# UCirKitUserStudy5-3.net
KiCad netlist of a schematic drawn in EAGLE
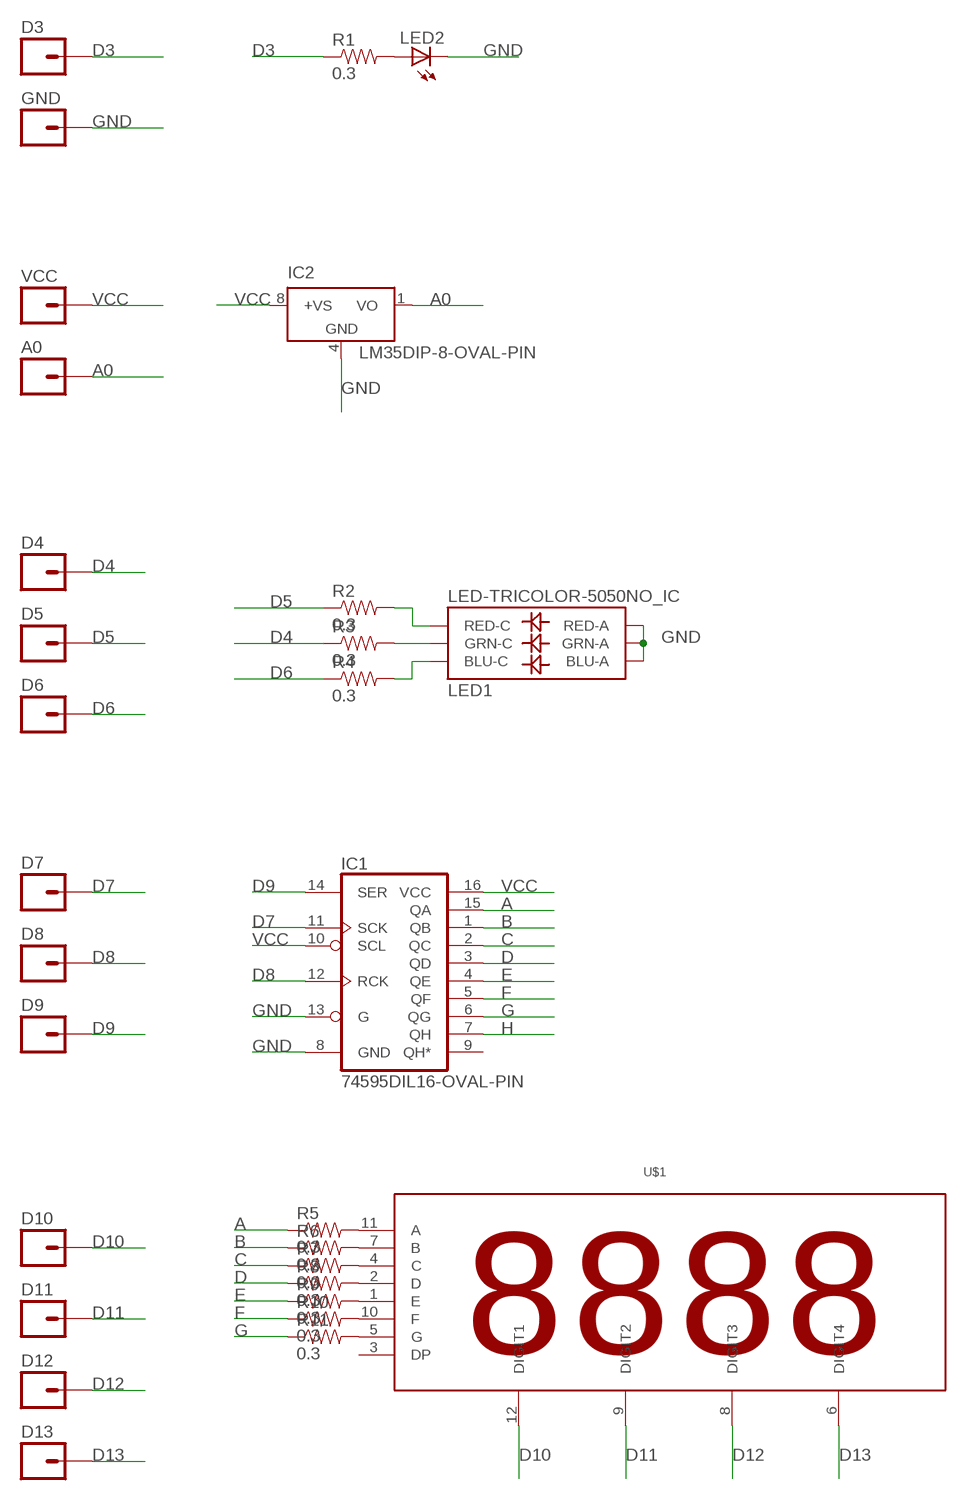
[diagram p0: schematic, sheet 1]

(export (version "E")
  (design (tool "Eeschema 10.0.6"))
  (components
    (comp (ref "A0")
      (value "M01OVAL_PIN")
      (footprint "eagle-import:1X01_OVAL_PIN")
      (libsource (lib "eagle-import") (part "M01OVAL_PIN"))
    )
    (comp (ref "D3")
      (value "M01OVAL_PIN")
      (footprint "eagle-import:1X01_OVAL_PIN")
      (libsource (lib "eagle-import") (part "M01OVAL_PIN"))
    )
    (comp (ref "D4")
      (value "M01OVAL_PIN")
      (footprint "eagle-import:1X01_OVAL_PIN")
      (libsource (lib "eagle-import") (part "M01OVAL_PIN"))
    )
    (comp (ref "D5")
      (value "M01OVAL_PIN")
      (footprint "eagle-import:1X01_OVAL_PIN")
      (libsource (lib "eagle-import") (part "M01OVAL_PIN"))
    )
    (comp (ref "D6")
      (value "M01OVAL_PIN")
      (footprint "eagle-import:1X01_OVAL_PIN")
      (libsource (lib "eagle-import") (part "M01OVAL_PIN"))
    )
    (comp (ref "D7")
      (value "M01OVAL_PIN")
      (footprint "eagle-import:1X01_OVAL_PIN")
      (libsource (lib "eagle-import") (part "M01OVAL_PIN"))
    )
    (comp (ref "D8")
      (value "M01OVAL_PIN")
      (footprint "eagle-import:1X01_OVAL_PIN")
      (libsource (lib "eagle-import") (part "M01OVAL_PIN"))
    )
    (comp (ref "D9")
      (value "M01OVAL_PIN")
      (footprint "eagle-import:1X01_OVAL_PIN")
      (libsource (lib "eagle-import") (part "M01OVAL_PIN"))
    )
    (comp (ref "D10")
      (value "M01OVAL_PIN")
      (footprint "eagle-import:1X01_OVAL_PIN")
      (libsource (lib "eagle-import") (part "M01OVAL_PIN"))
    )
    (comp (ref "D11")
      (value "M01OVAL_PIN")
      (footprint "eagle-import:1X01_OVAL_PIN")
      (libsource (lib "eagle-import") (part "M01OVAL_PIN"))
    )
    (comp (ref "D12")
      (value "M01OVAL_PIN")
      (footprint "eagle-import:1X01_OVAL_PIN")
      (libsource (lib "eagle-import") (part "M01OVAL_PIN"))
    )
    (comp (ref "D13")
      (value "M01OVAL_PIN")
      (footprint "eagle-import:1X01_OVAL_PIN")
      (libsource (lib "eagle-import") (part "M01OVAL_PIN"))
    )
    (comp (ref "GND")
      (value "M01OVAL_PIN")
      (footprint "eagle-import:1X01_OVAL_PIN")
      (libsource (lib "eagle-import") (part "M01OVAL_PIN"))
    )
    (comp (ref "IC1")
      (value "74595DIL16-OVAL-PIN")
      (footprint "eagle-import:DIL16-OVAL-PIN")
      (libsource (lib "eagle-import") (part "74595DIL16-OVAL-PIN"))
    )
    (comp (ref "IC2")
      (value "LM35DIP-8-OVAL-PIN")
      (footprint "eagle-import:DIP-8-OVAL-PIN")
      (libsource (lib "eagle-import") (part "LM35DIP-8-OVAL-PIN"))
    )
    (comp (ref "LED1")
      (value "LED-TRICOLOR-5050NO_IC")
      (footprint "eagle-import:LED-TRICOLOR-5050")
      (libsource (lib "eagle-import") (part "LED-TRICOLOR-5050NO_IC"))
    )
    (comp (ref "LED2")
      (value "LEDCHIP-LED0805")
      (footprint "eagle-import:CHIP-LED0805")
      (libsource (lib "eagle-import") (part "LEDCHIP-LED0805"))
    )
    (comp (ref "R1")
      (value "0.3")
      (footprint "eagle-import:0805")
      (libsource (lib "eagle-import") (part "0.3OHM-1/8W-1%(0805)"))
    )
    (comp (ref "R2")
      (value "0.3")
      (footprint "eagle-import:0805")
      (libsource (lib "eagle-import") (part "0.3OHM-1/8W-1%(0805)"))
    )
    (comp (ref "R3")
      (value "0.3")
      (footprint "eagle-import:0805")
      (libsource (lib "eagle-import") (part "0.3OHM-1/8W-1%(0805)"))
    )
    (comp (ref "R4")
      (value "0.3")
      (footprint "eagle-import:0805")
      (libsource (lib "eagle-import") (part "0.3OHM-1/8W-1%(0805)"))
    )
    (comp (ref "R5")
      (value "0.3")
      (footprint "eagle-import:0805")
      (libsource (lib "eagle-import") (part "0.3OHM-1/8W-1%(0805)"))
    )
    (comp (ref "R6")
      (value "0.3")
      (footprint "eagle-import:0805")
      (libsource (lib "eagle-import") (part "0.3OHM-1/8W-1%(0805)"))
    )
    (comp (ref "R7")
      (value "0.3")
      (footprint "eagle-import:0805")
      (libsource (lib "eagle-import") (part "0.3OHM-1/8W-1%(0805)"))
    )
    (comp (ref "R8")
      (value "0.3")
      (footprint "eagle-import:0805")
      (libsource (lib "eagle-import") (part "0.3OHM-1/8W-1%(0805)"))
    )
    (comp (ref "R9")
      (value "0.3")
      (footprint "eagle-import:0805")
      (libsource (lib "eagle-import") (part "0.3OHM-1/8W-1%(0805)"))
    )
    (comp (ref "R10")
      (value "0.3")
      (footprint "eagle-import:0805")
      (libsource (lib "eagle-import") (part "0.3OHM-1/8W-1%(0805)"))
    )
    (comp (ref "R11")
      (value "0.3")
      (footprint "eagle-import:0805")
      (libsource (lib "eagle-import") (part "0.3OHM-1/8W-1%(0805)"))
    )
    (comp (ref "U$1")
      (value "4DIGIT_SEVEN_SEGMENT4DIGIT_SEVEN_SEGMENT_OVAL_PIN")
      (footprint "eagle-import:4DIGIT_SEVEN_SEGMENT_OVAL_PIN")
      (libsource (lib "eagle-import") (part "4DIGIT_SEVEN_SEGMENT4DIGIT_SEVEN_SEGMENT_OVAL_PIN"))
    )
    (comp (ref "VCC")
      (value "M01OVAL_PIN")
      (footprint "eagle-import:1X01_OVAL_PIN")
      (libsource (lib "eagle-import") (part "M01OVAL_PIN"))
    )
  )
  (nets
    (net (code "1") (name "/A") (class "Default")
      (node (ref "IC1") (pin "15") (pinfunction "QA_15") (pintype "tri_state"))
      (node (ref "R5") (pin "1") (pinfunction "1_1") (pintype "passive"))
    )
    (net (code "2") (name "/A0") (class "Default")
      (node (ref "A0") (pin "1") (pinfunction "1_1") (pintype "passive"))
      (node (ref "IC2") (pin "1") (pinfunction "VO_1") (pintype "input"))
    )
    (net (code "3") (name "/B") (class "Default")
      (node (ref "IC1") (pin "1") (pinfunction "QB_1") (pintype "tri_state"))
      (node (ref "R6") (pin "1") (pinfunction "1_1") (pintype "passive"))
    )
    (net (code "4") (name "/C") (class "Default")
      (node (ref "IC1") (pin "2") (pinfunction "QC_2") (pintype "tri_state"))
      (node (ref "R7") (pin "1") (pinfunction "1_1") (pintype "passive"))
    )
    (net (code "5") (name "/D") (class "Default")
      (node (ref "IC1") (pin "3") (pinfunction "QD_3") (pintype "tri_state"))
      (node (ref "R8") (pin "1") (pinfunction "1_1") (pintype "passive"))
    )
    (net (code "6") (name "/D3") (class "Default")
      (node (ref "D3") (pin "1") (pinfunction "1_1") (pintype "passive"))
      (node (ref "R1") (pin "1") (pinfunction "1_1") (pintype "passive"))
    )
    (net (code "7") (name "/D4") (class "Default")
      (node (ref "D4") (pin "1") (pinfunction "1_1") (pintype "passive"))
      (node (ref "R3") (pin "1") (pinfunction "1_1") (pintype "passive"))
    )
    (net (code "8") (name "/D5") (class "Default")
      (node (ref "D5") (pin "1") (pinfunction "1_1") (pintype "passive"))
      (node (ref "R2") (pin "1") (pinfunction "1_1") (pintype "passive"))
    )
    (net (code "9") (name "/D6") (class "Default")
      (node (ref "D6") (pin "1") (pinfunction "1_1") (pintype "passive"))
      (node (ref "R4") (pin "1") (pinfunction "1_1") (pintype "passive"))
    )
    (net (code "10") (name "/D7") (class "Default")
      (node (ref "D7") (pin "1") (pinfunction "1_1") (pintype "passive"))
      (node (ref "IC1") (pin "11") (pinfunction "SCK_11") (pintype "input"))
    )
    (net (code "11") (name "/D8") (class "Default")
      (node (ref "D8") (pin "1") (pinfunction "1_1") (pintype "passive"))
      (node (ref "IC1") (pin "12") (pinfunction "RCK_12") (pintype "input"))
    )
    (net (code "12") (name "/D9") (class "Default")
      (node (ref "D9") (pin "1") (pinfunction "1_1") (pintype "passive"))
      (node (ref "IC1") (pin "14") (pinfunction "SER_14") (pintype "input"))
    )
    (net (code "13") (name "/D10") (class "Default")
      (node (ref "D10") (pin "1") (pinfunction "1_1") (pintype "passive"))
      (node (ref "U$1") (pin "12") (pinfunction "DIGIT1_12") (pintype "bidirectional"))
    )
    (net (code "14") (name "/D11") (class "Default")
      (node (ref "D11") (pin "1") (pinfunction "1_1") (pintype "passive"))
      (node (ref "U$1") (pin "9") (pinfunction "DIGIT2_9") (pintype "bidirectional"))
    )
    (net (code "15") (name "/D12") (class "Default")
      (node (ref "D12") (pin "1") (pinfunction "1_1") (pintype "passive"))
      (node (ref "U$1") (pin "8") (pinfunction "DIGIT3_8") (pintype "bidirectional"))
    )
    (net (code "16") (name "/D13") (class "Default")
      (node (ref "D13") (pin "1") (pinfunction "1_1") (pintype "passive"))
      (node (ref "U$1") (pin "6") (pinfunction "DIGIT4_6") (pintype "bidirectional"))
    )
    (net (code "17") (name "/E") (class "Default")
      (node (ref "IC1") (pin "4") (pinfunction "QE_4") (pintype "tri_state"))
      (node (ref "R9") (pin "1") (pinfunction "1_1") (pintype "passive"))
    )
    (net (code "18") (name "/F") (class "Default")
      (node (ref "IC1") (pin "5") (pinfunction "QF_5") (pintype "tri_state"))
      (node (ref "R10") (pin "1") (pinfunction "1_1") (pintype "passive"))
    )
    (net (code "19") (name "/G") (class "Default")
      (node (ref "IC1") (pin "6") (pinfunction "QG_6") (pintype "tri_state"))
      (node (ref "R11") (pin "1") (pinfunction "1_1") (pintype "passive"))
    )
    (net (code "20") (name "/GND") (class "Default")
      (node (ref "GND") (pin "1") (pinfunction "1_1") (pintype "passive"))
      (node (ref "IC1") (pin "13") (pinfunction "G_13") (pintype "input"))
      (node (ref "IC1") (pin "8") (pinfunction "GND_8") (pintype "power_in"))
      (node (ref "IC2") (pin "4") (pinfunction "GND_4") (pintype "power_in"))
      (node (ref "LED1") (pin "1") (pinfunction "GRN-A_1") (pintype "bidirectional"))
      (node (ref "LED1") (pin "2") (pinfunction "RED-A_2") (pintype "bidirectional"))
      (node (ref "LED1") (pin "3") (pinfunction "BLU-A_3") (pintype "bidirectional"))
      (node (ref "LED2") (pin "C") (pinfunction "C_C") (pintype "passive"))
    )
    (net (code "21") (name "/H") (class "Default")
      (node (ref "IC1") (pin "7") (pinfunction "QH_7") (pintype "tri_state"))
    )
    (net (code "22") (name "/VCC") (class "Default")
      (node (ref "IC1") (pin "10") (pinfunction "SCL_10") (pintype "input"))
      (node (ref "IC1") (pin "16") (pinfunction "VCC_16") (pintype "power_in"))
      (node (ref "IC2") (pin "8") (pinfunction "+VS_8") (pintype "input"))
      (node (ref "VCC") (pin "1") (pinfunction "1_1") (pintype "passive"))
    )
    (net (code "23") (name "Net-(LED1-BLU-C)") (class "Default")
      (node (ref "LED1") (pin "4") (pinfunction "BLU-C_4") (pintype "bidirectional"))
      (node (ref "R4") (pin "2") (pinfunction "2_2") (pintype "passive"))
    )
    (net (code "24") (name "Net-(LED1-GRN-C)") (class "Default")
      (node (ref "LED1") (pin "6") (pinfunction "GRN-C_6") (pintype "bidirectional"))
      (node (ref "R3") (pin "2") (pinfunction "2_2") (pintype "passive"))
    )
    (net (code "25") (name "Net-(LED1-RED-C)") (class "Default")
      (node (ref "LED1") (pin "5") (pinfunction "RED-C_5") (pintype "bidirectional"))
      (node (ref "R2") (pin "2") (pinfunction "2_2") (pintype "passive"))
    )
    (net (code "26") (name "Net-(LED2-PadA)") (class "Default")
      (node (ref "LED2") (pin "A") (pinfunction "A_A") (pintype "passive"))
      (node (ref "R1") (pin "2") (pinfunction "2_2") (pintype "passive"))
    )
    (net (code "27") (name "Net-(U$1-A)") (class "Default")
      (node (ref "R5") (pin "2") (pinfunction "2_2") (pintype "passive"))
      (node (ref "U$1") (pin "11") (pinfunction "A_11") (pintype "bidirectional"))
    )
    (net (code "28") (name "Net-(U$1-B)") (class "Default")
      (node (ref "R6") (pin "2") (pinfunction "2_2") (pintype "passive"))
      (node (ref "U$1") (pin "7") (pinfunction "B_7") (pintype "bidirectional"))
    )
    (net (code "29") (name "Net-(U$1-C)") (class "Default")
      (node (ref "R7") (pin "2") (pinfunction "2_2") (pintype "passive"))
      (node (ref "U$1") (pin "4") (pinfunction "C_4") (pintype "bidirectional"))
    )
    (net (code "30") (name "Net-(U$1-D)") (class "Default")
      (node (ref "R8") (pin "2") (pinfunction "2_2") (pintype "passive"))
      (node (ref "U$1") (pin "2") (pinfunction "D_2") (pintype "bidirectional"))
    )
    (net (code "31") (name "Net-(U$1-E)") (class "Default")
      (node (ref "R9") (pin "2") (pinfunction "2_2") (pintype "passive"))
      (node (ref "U$1") (pin "1") (pinfunction "E_1") (pintype "bidirectional"))
    )
    (net (code "32") (name "Net-(U$1-F)") (class "Default")
      (node (ref "R10") (pin "2") (pinfunction "2_2") (pintype "passive"))
      (node (ref "U$1") (pin "10") (pinfunction "F_10") (pintype "bidirectional"))
    )
    (net (code "33") (name "Net-(U$1-G)") (class "Default")
      (node (ref "R11") (pin "2") (pinfunction "2_2") (pintype "passive"))
      (node (ref "U$1") (pin "5") (pinfunction "G_5") (pintype "bidirectional"))
    )
    (net (code "34") (name "unconnected-(IC1-QH*-Pad9)") (class "Default")
      (node (ref "IC1") (pin "9") (pinfunction "QH*_9") (pintype "tri_state"))
    )
    (net (code "35") (name "unconnected-(U$1-DP-Pad3)") (class "Default")
      (node (ref "U$1") (pin "3") (pinfunction "DP_3") (pintype "bidirectional"))
    )
  )
)
